# Sheet.net
KiCad netlist of a schematic drawn in Altium Designer
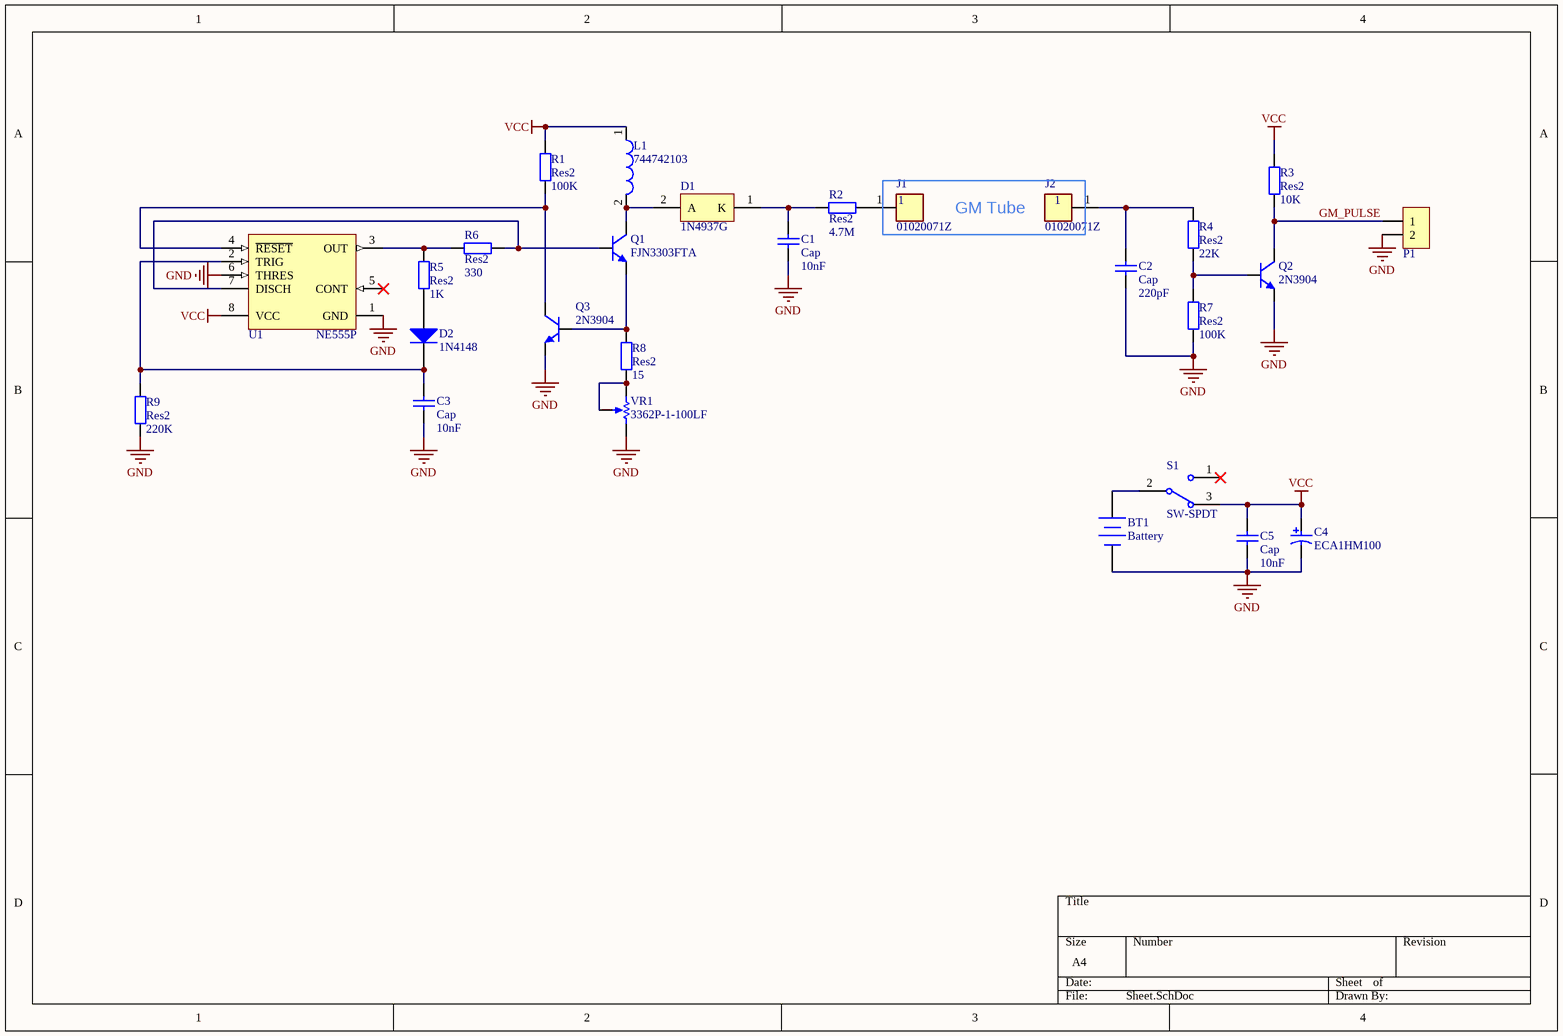
[diagram p0: Sheet.SchDoc]

(export (version "E")
  (design (tool "Eeschema 10.0.6"))
  (components
    (comp (ref "BT1")
      (value "Battery")
      (footprint "BAT-2")
      (description "Multicell Battery")
      (fields (field (name "PUBLISHER") "Altium Limited"))
      (libsource (lib "Miscellaneous Devices") (part "Battery"))
    )
    (comp (ref "C1")
      (value "Cap")
      (footprint "RAD-0.2")
      (description "Capacitor")
      (fields (field (name "ALTIUM_VALUE") "10nF") (field (name "PUBLISHER") "Altium Limited"))
      (libsource (lib "Miscellaneous Devices") (part "Cap"))
    )
    (comp (ref "C2")
      (value "Cap")
      (footprint "RAD-0.2")
      (description "Capacitor")
      (fields (field (name "ALTIUM_VALUE") "220pF") (field (name "PUBLISHER") "Altium Limited"))
      (libsource (lib "Miscellaneous Devices") (part "Cap"))
    )
    (comp (ref "C3")
      (value "Cap")
      (footprint "RAD-0.2")
      (description "Capacitor")
      (fields (field (name "ALTIUM_VALUE") "10nF") (field (name "PUBLISHER") "Altium Limited"))
      (libsource (lib "Miscellaneous Devices") (part "Cap"))
    )
    (comp (ref "C4")
      (value "ECA1HM100")
      (footprint "CAPPR55-200-1100X500X1200")
      (description "Aluminum Electrolytic Capacitor, 10 uF, +/- 20%, 50 V, -40 to 85 degC, 2-Pin THD, RoHS, Bulk")
      (fields (field (name "MANUFACTURER") "Panasonic") (field (name "TOLERANCE") "20%"))
      (libsource (lib "Altium Content Vault") (part "CAP-P-2"))
    )
    (comp (ref "C5")
      (value "Cap")
      (footprint "RAD-0.1")
      (description "Capacitor")
      (fields (field (name "ALTIUM_VALUE") "10nF") (field (name "PUBLISHER") "Altium Limited"))
      (libsource (lib "Miscellaneous Devices") (part "Cap"))
    )
    (comp (ref "D1")
      (value "1N4937G")
      (footprint "ONSC-AXIAL_LEAD-2-59-10_P")
      (description "Fast-Recovery Rectifier, 2-Pin Axial_Lead, Pb-Free, Bulk Bag")
      (fields (field (name "MANUFACTURER") "On Semiconductor"))
      (libsource (lib "Altium Content Vault") (part "ONSC-D-K1A2-2_A"))
    )
    (comp (ref "D2")
      (value "1N4148")
      (footprint "NXP-SOD27-2_V")
      (description "High-speed Diode, 100 V, 450 mA, 2-Pin SOD27, RoHS")
      (fields (field (name "MANUFACTURER") "NXP Semiconductors"))
      (libsource (lib "Altium Content Vault") (part "NXP-A1K2-2"))
    )
    (comp (ref "J1")
      (value "01020071Z")
      (footprint "FP-102-MFG")
      (description "FUSE CLIP CARTRIDGE 250V 15A PCB")
      (fields
        (field (name "MANUFACTURER") "Littelfuse Inc")
        (field (name "OCTOPART") "https://octopart.com/01020071z-littelfuse-18837869")
      )
      (libsource (lib "") (part "600373309f0643ccfefc365bd0e8f7b_1"))
    )
    (comp (ref "J2")
      (value "01020071Z")
      (footprint "FP-102-MFG")
      (description "FUSE CLIP CARTRIDGE 250V 15A PCB")
      (fields
        (field (name "MANUFACTURER") "Littelfuse Inc")
        (field (name "OCTOPART") "https://octopart.com/01020071z-littelfuse-18837869")
      )
      (libsource (lib "Altium Content Vault") (part "600373309f0643ccfefc365bd0e8f7b"))
    )
    (comp (ref "L1")
      (value "744742103")
      (footprint "WE-TI-L")
      (description "Radial Leaded Wire Wound Inductor WE-TI, L=10000 µH")
      (fields (field (name "MANUFACTURER") "Wuerth Elektronik"))
      (libsource (lib "Altium Content Vault") (part "PAS-IND-INDUCTOR-2"))
    )
    (comp (ref "P1")
      (value "HDR-1X2")
      (footprint "XH2.54-2P_H")
      (description "2P接插件")
      (fields (field (name "版权归属") "源创客"))
      (libsource (lib "接插件") (part "Header 2"))
    )
    (comp (ref "Q1")
      (value "FJN3303FTA")
      (footprint "TO92B")
      (description "高频放大-NPN型")
      (fields (field (name "版权归属") "源创客"))
      (libsource (lib "三极管") (part "8050-DIP"))
    )
    (comp (ref "Q2")
      (value "2N3904")
      (footprint "TO92B")
      (description "高频放大-NPN型")
      (fields (field (name "版权归属") "源创客"))
      (libsource (lib "三极管") (part "8050-DIP"))
    )
    (comp (ref "Q3")
      (value "2N3904")
      (footprint "TO92B")
      (description "高频放大-NPN型")
      (fields (field (name "版权归属") "源创客"))
      (libsource (lib "三极管") (part "8050-DIP"))
    )
    (comp (ref "R1")
      (value "Res2")
      (footprint "AXIAL-0.4")
      (description "Resistor")
      (fields (field (name "ALTIUM_VALUE") "100K") (field (name "PUBLISHER") "Altium Limited"))
      (libsource (lib "Miscellaneous Devices") (part "Res2"))
    )
    (comp (ref "R2")
      (value "Res2")
      (footprint "AXIAL-0.4")
      (description "Resistor")
      (fields (field (name "ALTIUM_VALUE") "4.7M") (field (name "PUBLISHER") "Altium Limited"))
      (libsource (lib "") (part "Res2_1"))
    )
    (comp (ref "R3")
      (value "Res2")
      (footprint "AXIAL-0.4")
      (description "Resistor")
      (fields (field (name "ALTIUM_VALUE") "10K") (field (name "PUBLISHER") "Altium Limited"))
      (libsource (lib "Miscellaneous Devices") (part "Res2"))
    )
    (comp (ref "R4")
      (value "Res2")
      (footprint "AXIAL-0.4")
      (description "Resistor")
      (fields (field (name "ALTIUM_VALUE") "22K") (field (name "PUBLISHER") "Altium Limited"))
      (libsource (lib "Miscellaneous Devices") (part "Res2"))
    )
    (comp (ref "R5")
      (value "Res2")
      (footprint "AXIAL-0.4")
      (description "Resistor")
      (fields (field (name "ALTIUM_VALUE") "1K") (field (name "PUBLISHER") "Altium Limited"))
      (libsource (lib "Miscellaneous Devices") (part "Res2"))
    )
    (comp (ref "R6")
      (value "Res2")
      (footprint "AXIAL-0.4")
      (description "Resistor")
      (fields (field (name "ALTIUM_VALUE") "330") (field (name "PUBLISHER") "Altium Limited"))
      (libsource (lib "") (part "Res2_2"))
    )
    (comp (ref "R7")
      (value "Res2")
      (footprint "AXIAL-0.4")
      (description "Resistor")
      (fields (field (name "ALTIUM_VALUE") "100K") (field (name "PUBLISHER") "Altium Limited"))
      (libsource (lib "Miscellaneous Devices") (part "Res2"))
    )
    (comp (ref "R8")
      (value "Res2")
      (footprint "AXIAL-0.4")
      (description "Resistor")
      (fields (field (name "ALTIUM_VALUE") "15") (field (name "PUBLISHER") "Altium Limited"))
      (libsource (lib "Miscellaneous Devices") (part "Res2"))
    )
    (comp (ref "R9")
      (value "Res2")
      (footprint "AXIAL-0.4")
      (description "Resistor")
      (fields (field (name "ALTIUM_VALUE") "220K") (field (name "PUBLISHER") "Altium Limited"))
      (libsource (lib "Miscellaneous Devices") (part "Res2"))
    )
    (comp (ref "S1")
      (value "SW-SPDT")
      (footprint "SW-TH_SK12D07VG4")
      (description "SPDT Subminiature Toggle Switch, Right Angle Mounting, Vertical Actuation")
      (fields (field (name "PUBLISHER") "Altium Limited"))
      (libsource (lib "Miscellaneous Devices") (part "SW-SPDT"))
    )
    (comp (ref "U1")
      (value "NE555P")
      (footprint "P0008A")
      (description "Precision Timer, 4.5 to 16 V, 0 to 70 degC, 8-Pin DIP, Pb-Free, Tube")
      (fields (field (name "MANUFACTURER") "TexasInstruments"))
      (libsource (lib "Altium Content Vault") (part "TI-NE555-P8"))
    )
    (comp (ref "VR1")
      (value "3362P-1-100LF")
      (footprint "BOUR-3362P")
      (fields (field (name "TOLERANCE") "1%"))
      (libsource (lib "Altium Content Vault") (part "RES-POT-3"))
    )
  )
  (nets
    (net (code "1") (name "/GM_PULSE") (class "Default")
      (node (ref "P1") (pin "1") (pinfunction "1_1") (pintype "passive"))
      (node (ref "Q2") (pin "3") (pinfunction "C_3") (pintype "passive"))
      (node (ref "R3") (pin "1") (pinfunction "1_1") (pintype "passive"))
    )
    (net (code "2") (name "GND") (class "Default")
      (node (ref "BT1") (pin "2") (pinfunction "-_2") (pintype "passive"))
      (node (ref "C1") (pin "1") (pinfunction "1_1") (pintype "passive"))
      (node (ref "C2") (pin "1") (pinfunction "1_1") (pintype "passive"))
      (node (ref "C3") (pin "1") (pinfunction "1_1") (pintype "passive"))
      (node (ref "C4") (pin "2") (pinfunction "2_2") (pintype "passive"))
      (node (ref "C5") (pin "1") (pinfunction "1_1") (pintype "passive"))
      (node (ref "P1") (pin "2") (pinfunction "2_2") (pintype "passive"))
      (node (ref "Q2") (pin "1") (pinfunction "E_1") (pintype "passive"))
      (node (ref "Q3") (pin "1") (pinfunction "E_1") (pintype "passive"))
      (node (ref "R7") (pin "1") (pinfunction "1_1") (pintype "passive"))
      (node (ref "R9") (pin "1") (pinfunction "1_1") (pintype "passive"))
      (node (ref "U1") (pin "1") (pinfunction "GND_1") (pintype "power_in"))
      (node (ref "U1") (pin "6") (pinfunction "THRES_6") (pintype "input"))
      (node (ref "VR1") (pin "3") (pinfunction "CW_3") (pintype "passive"))
    )
    (net (code "3") (name "Net-(BT1-+)") (class "Default")
      (node (ref "BT1") (pin "1") (pinfunction "+_1") (pintype "passive"))
      (node (ref "S1") (pin "2") (pinfunction "2_2") (pintype "passive"))
    )
    (net (code "4") (name "Net-(C2-Pad2)") (class "Default")
      (node (ref "C2") (pin "2") (pinfunction "2_2") (pintype "passive"))
      (node (ref "J2") (pin "1") (pinfunction "1_1") (pintype "passive"))
      (node (ref "R4") (pin "2") (pinfunction "2_2") (pintype "passive"))
    )
    (net (code "5") (name "Net-(D1-A)") (class "Default")
      (node (ref "D1") (pin "2") (pinfunction "A_2") (pintype "passive"))
      (node (ref "L1") (pin "2") (pinfunction "2_2") (pintype "passive"))
      (node (ref "Q1") (pin "3") (pinfunction "C_3") (pintype "passive"))
    )
    (net (code "6") (name "Net-(D1-K)") (class "Default")
      (node (ref "C1") (pin "2") (pinfunction "2_2") (pintype "passive"))
      (node (ref "D1") (pin "1") (pinfunction "K_1") (pintype "passive"))
      (node (ref "R2") (pin "2") (pinfunction "2_2") (pintype "passive"))
    )
    (net (code "7") (name "Net-(D2-A)") (class "Default")
      (node (ref "D2") (pin "1") (pinfunction "A_1") (pintype "passive"))
      (node (ref "R5") (pin "1") (pinfunction "1_1") (pintype "passive"))
    )
    (net (code "8") (name "Net-(D2-K)") (class "Default")
      (node (ref "C3") (pin "2") (pinfunction "2_2") (pintype "passive"))
      (node (ref "D2") (pin "2") (pinfunction "K_2") (pintype "passive"))
      (node (ref "R9") (pin "2") (pinfunction "2_2") (pintype "passive"))
      (node (ref "U1") (pin "2") (pinfunction "TRIG_2") (pintype "input"))
    )
    (net (code "9") (name "Net-(J1-Pad1)") (class "Default")
      (node (ref "J1") (pin "1") (pinfunction "1_1") (pintype "passive"))
      (node (ref "R2") (pin "1") (pinfunction "1_1") (pintype "passive"))
    )
    (net (code "10") (name "Net-(Q1-B)") (class "Default")
      (node (ref "Q1") (pin "2") (pinfunction "B_2") (pintype "passive"))
      (node (ref "R6") (pin "2") (pinfunction "2_2") (pintype "passive"))
      (node (ref "U1") (pin "7") (pinfunction "DISCH_7") (pintype "open_collector"))
    )
    (net (code "11") (name "Net-(Q1-E)") (class "Default")
      (node (ref "Q1") (pin "1") (pinfunction "E_1") (pintype "passive"))
      (node (ref "Q3") (pin "2") (pinfunction "B_2") (pintype "passive"))
      (node (ref "R8") (pin "2") (pinfunction "2_2") (pintype "passive"))
    )
    (net (code "12") (name "Net-(Q2-B)") (class "Default")
      (node (ref "Q2") (pin "2") (pinfunction "B_2") (pintype "passive"))
      (node (ref "R4") (pin "1") (pinfunction "1_1") (pintype "passive"))
      (node (ref "R7") (pin "2") (pinfunction "2_2") (pintype "passive"))
    )
    (net (code "13") (name "Net-(Q3-C)") (class "Default")
      (node (ref "Q3") (pin "3") (pinfunction "C_3") (pintype "passive"))
      (node (ref "R1") (pin "1") (pinfunction "1_1") (pintype "passive"))
      (node (ref "U1") (pin "4") (pinfunction "~{RESET}_4") (pintype "input"))
    )
    (net (code "14") (name "Net-(U1-OUT)") (class "Default")
      (node (ref "R5") (pin "2") (pinfunction "2_2") (pintype "passive"))
      (node (ref "R6") (pin "1") (pinfunction "1_1") (pintype "passive"))
      (node (ref "U1") (pin "3") (pinfunction "OUT_3") (pintype "output"))
    )
    (net (code "15") (name "Net-(VR1-CCW)") (class "Default")
      (node (ref "R8") (pin "1") (pinfunction "1_1") (pintype "passive"))
      (node (ref "VR1") (pin "1") (pinfunction "CCW_1") (pintype "passive"))
      (node (ref "VR1") (pin "2") (pinfunction "S_2") (pintype "passive"))
    )
    (net (code "16") (name "VCC") (class "Default")
      (node (ref "C4") (pin "1") (pinfunction "1_1") (pintype "passive"))
      (node (ref "C5") (pin "2") (pinfunction "2_2") (pintype "passive"))
      (node (ref "L1") (pin "1") (pinfunction "1_1") (pintype "passive"))
      (node (ref "R1") (pin "2") (pinfunction "2_2") (pintype "passive"))
      (node (ref "R3") (pin "2") (pinfunction "2_2") (pintype "passive"))
      (node (ref "S1") (pin "3") (pinfunction "3_3") (pintype "passive"))
      (node (ref "U1") (pin "8") (pinfunction "VCC_8") (pintype "power_in"))
    )
    (net (code "17") (name "unconnected-(S1-Pad1)") (class "Default")
      (node (ref "S1") (pin "1") (pinfunction "1_1") (pintype "passive+no_connect"))
    )
    (net (code "18") (name "unconnected-(U1-CONT-Pad5)") (class "Default")
      (node (ref "U1") (pin "5") (pinfunction "CONT_5") (pintype "input+no_connect"))
    )
  )
)
